# Connector.net
KiCad netlist of a schematic drawn in Altium Designer
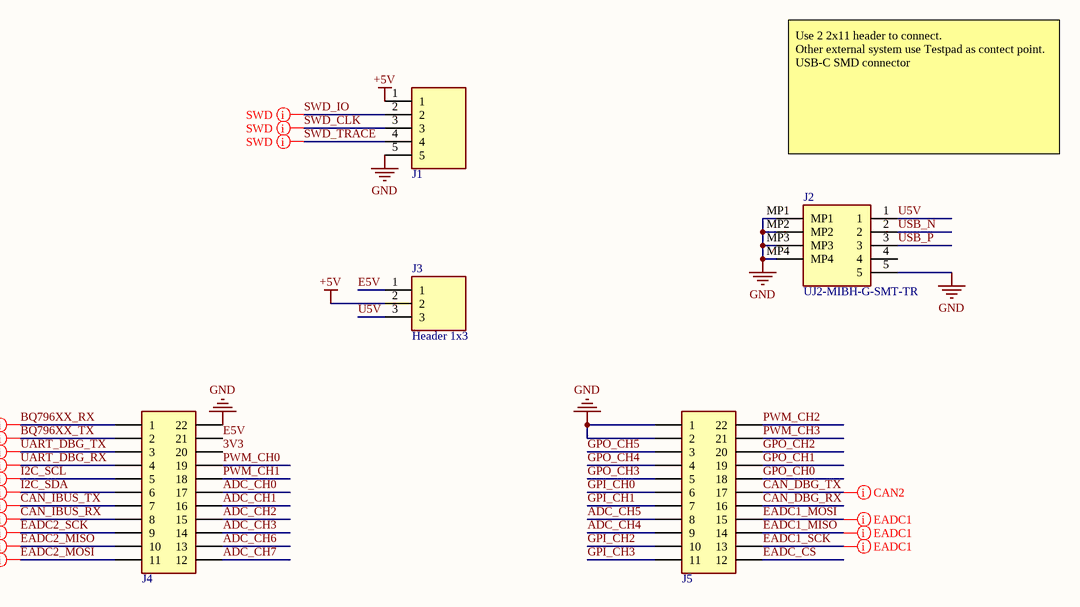
[diagram p0: Connector.SchDoc]

(export (version "E")
  (design (tool "Eeschema 10.0.6"))
  (components
    (comp (ref "J1")
      (value "Header 1x5")
      (footprint "HDR_1X5_2.54_SMD")
      (fields (field (name "MANUFACTURER_PART_NUMBER") "87224-5"))
      (libsource (lib "BMS_ShareComponentLibrary") (part "Header 1x5"))
    )
    (comp (ref "J2")
      (value "UJ2-MIBH-G-SMT-TR")
      (footprint "USB_B_5P_SMD")
      (description "USB Connectors USB jack, 2.0, micro B type, 5 pin, horizontal, gold flash, SMT, TR")
      (fields (field (name "MOUSER PART NUMBER") "490-UJ2-MIBH-G-SMTTR"))
      (libsource (lib "BMS_ShareComponentLibrary") (part "USB_B 5P"))
    )
    (comp (ref "J3")
      (value "Header 1x3")
      (footprint "HDR_1X3_2.54_THD")
      (description "Pin Header 2.54mm Pitch STR DIP, 1x3Pin, G/F, LCP, 8.08mm*2.54mm*3.18mm, Color-Black, Bag")
      (fields
        (field (name "MOUSER PART NUMBER") "523-G800LR305018EU")
        (field (name "MANUFACTURER_PART_NUMBER") "G800LR305018EU")
      )
      (libsource (lib "BMS_ShareComponentLibrary") (part "Header 1x3"))
    )
    (comp (ref "J4")
      (value "Header 1x5")
      (footprint "HDR_2x11_2.54_THD")
      (description "Header 2x11")
      (libsource (lib "BMS_ShareComponentLibrary") (part "Header 2x11"))
    )
    (comp (ref "J5")
      (value "Header 1x5")
      (footprint "HDR_2x11_2.54_THD")
      (description "Header 2x11")
      (libsource (lib "BMS_ShareComponentLibrary") (part "Header 2x11"))
    )
  )
  (nets
    (net (code "1") (name "+5V") (class "Default")
      (node (ref "J1") (pin "1") (pinfunction "1_1") (pintype "passive"))
      (node (ref "J3") (pin "2") (pinfunction "2_2") (pintype "passive"))
    )
    (net (code "2") (name "/3V3") (class "Default")
      (node (ref "J4") (pin "20") (pinfunction "20_20") (pintype "passive"))
    )
    (net (code "3") (name "/ADC_CH0") (class "Default")
      (node (ref "J4") (pin "17") (pinfunction "17_17") (pintype "passive"))
    )
    (net (code "4") (name "/ADC_CH1") (class "Default")
      (node (ref "J4") (pin "16") (pinfunction "16_16") (pintype "passive"))
    )
    (net (code "5") (name "/ADC_CH2") (class "Default")
      (node (ref "J4") (pin "15") (pinfunction "15_15") (pintype "passive"))
    )
    (net (code "6") (name "/ADC_CH3") (class "Default")
      (node (ref "J4") (pin "14") (pinfunction "14_14") (pintype "passive"))
    )
    (net (code "7") (name "/ADC_CH4") (class "Default")
      (node (ref "J5") (pin "9") (pinfunction "9_9") (pintype "passive"))
    )
    (net (code "8") (name "/ADC_CH5") (class "Default")
      (node (ref "J5") (pin "8") (pinfunction "8_8") (pintype "passive"))
    )
    (net (code "9") (name "/ADC_CH6") (class "Default")
      (node (ref "J4") (pin "13") (pinfunction "13_13") (pintype "passive"))
    )
    (net (code "10") (name "/ADC_CH7") (class "Default")
      (node (ref "J4") (pin "12") (pinfunction "12_12") (pintype "passive"))
    )
    (net (code "11") (name "/BQ796XX_RX") (class "Default")
      (node (ref "J4") (pin "1") (pinfunction "1_1") (pintype "passive"))
    )
    (net (code "12") (name "/BQ796XX_TX") (class "Default")
      (node (ref "J4") (pin "2") (pinfunction "2_2") (pintype "passive"))
    )
    (net (code "13") (name "/CAN_DBG_RX") (class "Default")
      (node (ref "J5") (pin "16") (pinfunction "16_16") (pintype "passive"))
    )
    (net (code "14") (name "/CAN_DBG_TX") (class "Default")
      (node (ref "J5") (pin "17") (pinfunction "17_17") (pintype "passive"))
    )
    (net (code "15") (name "/CAN_IBUS_RX") (class "Default")
      (node (ref "J4") (pin "8") (pinfunction "8_8") (pintype "passive"))
    )
    (net (code "16") (name "/CAN_IBUS_TX") (class "Default")
      (node (ref "J4") (pin "7") (pinfunction "7_7") (pintype "passive"))
    )
    (net (code "17") (name "/E5V") (class "Default")
      (node (ref "J3") (pin "1") (pinfunction "1_1") (pintype "passive"))
      (node (ref "J4") (pin "21") (pinfunction "21_21") (pintype "passive"))
    )
    (net (code "18") (name "/EADC1_MISO") (class "Default")
      (node (ref "J5") (pin "14") (pinfunction "14_14") (pintype "passive"))
    )
    (net (code "19") (name "/EADC1_MOSI") (class "Default")
      (node (ref "J5") (pin "15") (pinfunction "15_15") (pintype "passive"))
    )
    (net (code "20") (name "/EADC1_SCK") (class "Default")
      (node (ref "J5") (pin "13") (pinfunction "13_13") (pintype "passive"))
    )
    (net (code "21") (name "/EADC2_MISO") (class "Default")
      (node (ref "J4") (pin "10") (pinfunction "10_10") (pintype "passive"))
    )
    (net (code "22") (name "/EADC2_MOSI") (class "Default")
      (node (ref "J4") (pin "11") (pinfunction "11_11") (pintype "passive"))
    )
    (net (code "23") (name "/EADC2_SCK") (class "Default")
      (node (ref "J4") (pin "9") (pinfunction "9_9") (pintype "passive"))
    )
    (net (code "24") (name "/EADC_CS") (class "Default")
      (node (ref "J5") (pin "12") (pinfunction "12_12") (pintype "passive"))
    )
    (net (code "25") (name "/GPI_CH0") (class "Default")
      (node (ref "J5") (pin "6") (pinfunction "6_6") (pintype "passive"))
    )
    (net (code "26") (name "/GPI_CH1") (class "Default")
      (node (ref "J5") (pin "7") (pinfunction "7_7") (pintype "passive"))
    )
    (net (code "27") (name "/GPI_CH2") (class "Default")
      (node (ref "J5") (pin "10") (pinfunction "10_10") (pintype "passive"))
    )
    (net (code "28") (name "/GPI_CH3") (class "Default")
      (node (ref "J5") (pin "11") (pinfunction "11_11") (pintype "passive"))
    )
    (net (code "29") (name "/GPO_CH0") (class "Default")
      (node (ref "J5") (pin "18") (pinfunction "18_18") (pintype "passive"))
    )
    (net (code "30") (name "/GPO_CH1") (class "Default")
      (node (ref "J5") (pin "19") (pinfunction "19_19") (pintype "passive"))
    )
    (net (code "31") (name "/GPO_CH2") (class "Default")
      (node (ref "J5") (pin "20") (pinfunction "20_20") (pintype "passive"))
    )
    (net (code "32") (name "/GPO_CH3") (class "Default")
      (node (ref "J5") (pin "5") (pinfunction "5_5") (pintype "passive"))
    )
    (net (code "33") (name "/GPO_CH4") (class "Default")
      (node (ref "J5") (pin "4") (pinfunction "4_4") (pintype "passive"))
    )
    (net (code "34") (name "/GPO_CH5") (class "Default")
      (node (ref "J5") (pin "3") (pinfunction "3_3") (pintype "passive"))
    )
    (net (code "35") (name "/I2C_SCL") (class "Default")
      (node (ref "J4") (pin "5") (pinfunction "5_5") (pintype "passive"))
    )
    (net (code "36") (name "/I2C_SDA") (class "Default")
      (node (ref "J4") (pin "6") (pinfunction "6_6") (pintype "passive"))
    )
    (net (code "37") (name "/PWM_CH0") (class "Default")
      (node (ref "J4") (pin "19") (pinfunction "19_19") (pintype "passive"))
    )
    (net (code "38") (name "/PWM_CH1") (class "Default")
      (node (ref "J4") (pin "18") (pinfunction "18_18") (pintype "passive"))
    )
    (net (code "39") (name "/PWM_CH2") (class "Default")
      (node (ref "J5") (pin "22") (pinfunction "22_22") (pintype "passive"))
    )
    (net (code "40") (name "/PWM_CH3") (class "Default")
      (node (ref "J5") (pin "21") (pinfunction "21_21") (pintype "passive"))
    )
    (net (code "41") (name "/SWD_CLK") (class "Default")
      (node (ref "J1") (pin "3") (pinfunction "3_3") (pintype "passive"))
    )
    (net (code "42") (name "/SWD_IO") (class "Default")
      (node (ref "J1") (pin "2") (pinfunction "2_2") (pintype "passive"))
    )
    (net (code "43") (name "/SWD_TRACE") (class "Default")
      (node (ref "J1") (pin "4") (pinfunction "4_4") (pintype "passive"))
    )
    (net (code "44") (name "/U5V") (class "Default")
      (node (ref "J2") (pin "1") (pinfunction "1_1") (pintype "passive"))
      (node (ref "J3") (pin "3") (pinfunction "3_3") (pintype "passive"))
    )
    (net (code "45") (name "/UART_DBG_RX") (class "Default")
      (node (ref "J4") (pin "4") (pinfunction "4_4") (pintype "passive"))
    )
    (net (code "46") (name "/UART_DBG_TX") (class "Default")
      (node (ref "J4") (pin "3") (pinfunction "3_3") (pintype "passive"))
    )
    (net (code "47") (name "/USB_N") (class "Default")
      (node (ref "J2") (pin "2") (pinfunction "2_2") (pintype "passive"))
    )
    (net (code "48") (name "/USB_P") (class "Default")
      (node (ref "J2") (pin "3") (pinfunction "3_3") (pintype "passive"))
    )
    (net (code "49") (name "GND") (class "Default")
      (node (ref "J1") (pin "5") (pinfunction "5_5") (pintype "passive"))
      (node (ref "J2") (pin "5") (pinfunction "5_5") (pintype "passive"))
      (node (ref "J2") (pin "MP1") (pinfunction "MP1_MP1") (pintype "passive"))
      (node (ref "J2") (pin "MP2") (pinfunction "MP2_MP2") (pintype "passive"))
      (node (ref "J2") (pin "MP3") (pinfunction "MP3_MP3") (pintype "passive"))
      (node (ref "J2") (pin "MP4") (pinfunction "MP4_MP4") (pintype "passive"))
      (node (ref "J4") (pin "22") (pinfunction "22_22") (pintype "passive"))
      (node (ref "J5") (pin "1") (pinfunction "1_1") (pintype "passive"))
      (node (ref "J5") (pin "2") (pinfunction "2_2") (pintype "passive"))
    )
    (net (code "50") (name "unconnected-(J2-Pad4)") (class "Default")
      (node (ref "J2") (pin "4") (pinfunction "4_4") (pintype "passive"))
    )
  )
)
